# display.net
KiCad netlist of a schematic drawn in Altium Designer
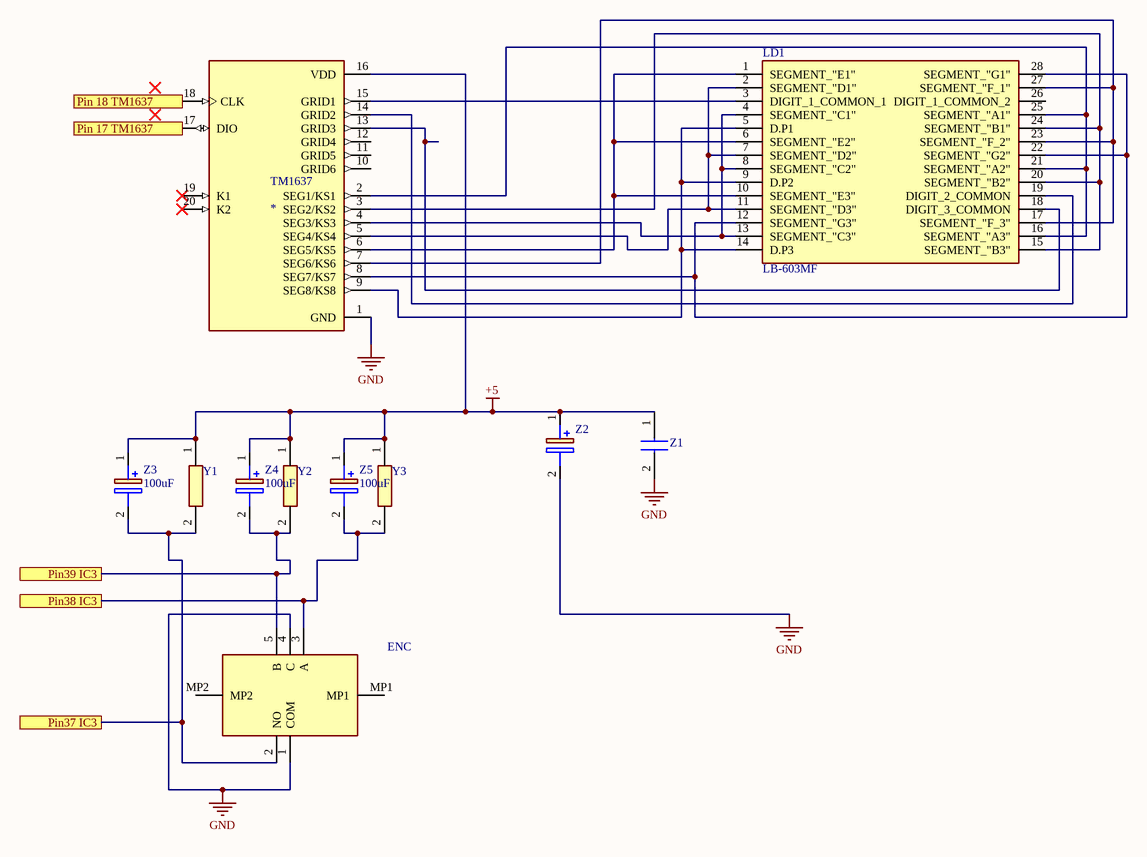
[diagram p0: display.SchDoc]

(export (version "E")
  (design (tool "Eeschema 10.0.6"))
  (components
    (comp (ref "ENC")
      (value "482016514001")
      (footprint "SamacSys:482016514001")
      (description "Switch")
      (fields (field (name "MOUSER2 PART NUMBER") "710-482016514001"))
      (libsource (lib "SamacSys") (part "482016514001"))
    )
    (comp (ref "LD1")
      (value "LB-603MF")
      (footprint "SamacSys:DIP1524W50P254L3750H820Q28N")
      (description "Display")
      (libsource (lib "*") (part "LB-603MF"))
    )
    (comp (ref "TM1637")
      (value "*")
      (footprint "DIP778W43P254L2612H431Q20N")
      (description "LED Drive Control Special Circuit")
      (fields (field (name "MF") "Titan Micro Electronics") (field (name "MP") "TM1637"))
      (libsource (lib "*") (part "TM1637"))
    )
    (comp (ref "Y1")
      (value "ESR10EZPJ183")
      (footprint "SamacSys:RESC2012X60N")
      (description "Resistor SMD 0805 10k")
      (libsource (lib "*") (part "ESR10EZPJ183"))
    )
    (comp (ref "Y2")
      (value "ESR10EZPJ183")
      (footprint "SamacSys:RESC2012X60N")
      (description "Resistor SMD 0805 10k")
      (libsource (lib "*") (part "ESR10EZPJ183"))
    )
    (comp (ref "Y3")
      (value "ESR10EZPJ183")
      (footprint "SamacSys:RESC2012X60N")
      (description "Resistor SMD 0805 10k")
      (libsource (lib "*") (part "ESR10EZPJ183"))
    )
    (comp (ref "Z1")
      (value "860010683032")
      (footprint "SamacSys:CAPPRD200W55D500H1200")
      (description "Capacitor C1")
      (libsource (lib "*") (part "860010683032"))
    )
    (comp (ref "Z2")
      (value "860240672002")
      (footprint "SamacSys:CAPC2012X90N")
      (description "Capacitor Polarised")
      (libsource (lib "*") (part "860240672002"))
    )
    (comp (ref "Z3")
      (value "100uF")
      (footprint "SamacSys:CAPC2012X90N")
      (description "Capacitor Polarised C4 3,5mm 8x11mm")
      (fields (field (name "MANUFACTURER_PART_NUMBER") "ECA-1HHG2R2B"))
      (libsource (lib "*") (part "ECA-1HHG2R2B"))
    )
    (comp (ref "Z4")
      (value "100uF")
      (footprint "SamacSys:CAPC2012X90N")
      (description "Capacitor Polarised C4 3,5mm 8x11mm")
      (fields (field (name "MANUFACTURER_PART_NUMBER") "ECA-1HHG2R2B"))
      (libsource (lib "*") (part "ECA-1HHG2R2B"))
    )
    (comp (ref "Z5")
      (value "100uF")
      (footprint "SamacSys:CAPC2012X90N")
      (description "Capacitor Polarised C4 3,5mm 8x11mm")
      (fields (field (name "MANUFACTURER_PART_NUMBER") "ECA-1HHG2R2B"))
      (libsource (lib "*") (part "ECA-1HHG2R2B"))
    )
  )
  (nets
    (net (code "1") (name "+5") (class "Default")
      (node (ref "TM1637") (pin "16") (pinfunction "VDD_16") (pintype "passive"))
      (node (ref "Y1") (pin "1") (pinfunction "1_1") (pintype "passive"))
      (node (ref "Y2") (pin "1") (pinfunction "1_1") (pintype "passive"))
      (node (ref "Y3") (pin "1") (pinfunction "1_1") (pintype "passive"))
      (node (ref "Z1") (pin "1") (pinfunction "+_1") (pintype "power_in"))
      (node (ref "Z2") (pin "1") (pinfunction "+_1") (pintype "passive"))
      (node (ref "Z3") (pin "1") (pinfunction "+_1") (pintype "passive"))
      (node (ref "Z4") (pin "1") (pinfunction "+_1") (pintype "passive"))
      (node (ref "Z5") (pin "1") (pinfunction "+_1") (pintype "passive"))
    )
    (net (code "2") (name "/Pin 17 TM1637") (class "Default")
      (node (ref "TM1637") (pin "17") (pinfunction "DIO_17") (pintype "bidirectional"))
    )
    (net (code "3") (name "/Pin 18 TM1637") (class "Default")
      (node (ref "TM1637") (pin "18") (pinfunction "CLK_18") (pintype "input"))
    )
    (net (code "4") (name "/Pin37 IC3") (class "Default")
      (node (ref "ENC") (pin "2") (pinfunction "NO_2") (pintype "passive"))
      (node (ref "Y1") (pin "2") (pinfunction "2_2") (pintype "passive"))
      (node (ref "Z3") (pin "2") (pinfunction "-_2") (pintype "passive"))
    )
    (net (code "5") (name "/Pin38 IC3") (class "Default")
      (node (ref "ENC") (pin "3") (pinfunction "A_3") (pintype "passive"))
      (node (ref "Y3") (pin "2") (pinfunction "2_2") (pintype "passive"))
      (node (ref "Z5") (pin "2") (pinfunction "-_2") (pintype "passive"))
    )
    (net (code "6") (name "/Pin39 IC3") (class "Default")
      (node (ref "ENC") (pin "5") (pinfunction "B_5") (pintype "passive"))
      (node (ref "Y2") (pin "2") (pinfunction "2_2") (pintype "passive"))
      (node (ref "Z4") (pin "2") (pinfunction "-_2") (pintype "passive"))
    )
    (net (code "7") (name "GND") (class "Default")
      (node (ref "ENC") (pin "1") (pinfunction "COM_1") (pintype "passive"))
      (node (ref "ENC") (pin "4") (pinfunction "C_4") (pintype "passive"))
      (node (ref "TM1637") (pin "1") (pinfunction "GND_1") (pintype "power_in"))
      (node (ref "Z1") (pin "2") (pinfunction "-_2") (pintype "power_in"))
      (node (ref "Z2") (pin "2") (pinfunction "-_2") (pintype "passive"))
    )
    (net (code "8") (name "Net-(LD1-D.P1)") (class "Default")
      (node (ref "LD1") (pin "14") (pinfunction "D.P3_14") (pintype "passive"))
      (node (ref "LD1") (pin "5") (pinfunction "D.P1_5") (pintype "passive"))
      (node (ref "LD1") (pin "9") (pinfunction "D.P2_9") (pintype "passive"))
      (node (ref "TM1637") (pin "9") (pinfunction "SEG8/KS8_9") (pintype "output"))
    )
    (net (code "9") (name "Net-(LD1-DIGIT_1_COMMON_1)") (class "Default")
      (node (ref "LD1") (pin "3") (pinfunction "DIGIT_1_COMMON_1_3") (pintype "passive"))
      (node (ref "TM1637") (pin "15") (pinfunction "GRID1_15") (pintype "output"))
    )
    (net (code "10") (name "Net-(LD1-DIGIT_2_COMMON)") (class "Default")
      (node (ref "LD1") (pin "19") (pinfunction "DIGIT_2_COMMON_19") (pintype "passive"))
      (node (ref "TM1637") (pin "14") (pinfunction "GRID2_14") (pintype "output"))
    )
    (net (code "11") (name "Net-(LD1-DIGIT_3_COMMON)") (class "Default")
      (node (ref "LD1") (pin "18") (pinfunction "DIGIT_3_COMMON_18") (pintype "passive"))
      (node (ref "TM1637") (pin "13") (pinfunction "GRID3_13") (pintype "output"))
    )
    (net (code "12") (name "Net-(LD1-SEGMENT_\"A1\")") (class "Default")
      (node (ref "LD1") (pin "16") (pinfunction "SEGMENT_\"A3\"_16") (pintype "passive"))
      (node (ref "LD1") (pin "21") (pinfunction "SEGMENT_\"A2\"_21") (pintype "passive"))
      (node (ref "LD1") (pin "25") (pinfunction "SEGMENT_\"A1\"_25") (pintype "passive"))
      (node (ref "TM1637") (pin "2") (pinfunction "SEG1/KS1_2") (pintype "output"))
    )
    (net (code "13") (name "Net-(LD1-SEGMENT_\"B1\")") (class "Default")
      (node (ref "LD1") (pin "15") (pinfunction "SEGMENT_\"B3\"_15") (pintype "passive"))
      (node (ref "LD1") (pin "20") (pinfunction "SEGMENT_\"B2\"_20") (pintype "passive"))
      (node (ref "LD1") (pin "24") (pinfunction "SEGMENT_\"B1\"_24") (pintype "passive"))
      (node (ref "TM1637") (pin "3") (pinfunction "SEG2/KS2_3") (pintype "output"))
    )
    (net (code "14") (name "Net-(LD1-SEGMENT_\"C1\")") (class "Default")
      (node (ref "LD1") (pin "13") (pinfunction "SEGMENT_\"C3\"_13") (pintype "passive"))
      (node (ref "LD1") (pin "4") (pinfunction "SEGMENT_\"C1\"_4") (pintype "passive"))
      (node (ref "LD1") (pin "8") (pinfunction "SEGMENT_\"C2\"_8") (pintype "passive"))
      (node (ref "TM1637") (pin "4") (pinfunction "SEG3/KS3_4") (pintype "output"))
    )
    (net (code "15") (name "Net-(LD1-SEGMENT_\"D1\")") (class "Default")
      (node (ref "LD1") (pin "11") (pinfunction "SEGMENT_\"D3\"_11") (pintype "passive"))
      (node (ref "LD1") (pin "2") (pinfunction "SEGMENT_\"D1\"_2") (pintype "passive"))
      (node (ref "LD1") (pin "7") (pinfunction "SEGMENT_\"D2\"_7") (pintype "passive"))
      (node (ref "TM1637") (pin "5") (pinfunction "SEG4/KS4_5") (pintype "output"))
    )
    (net (code "16") (name "Net-(LD1-SEGMENT_\"E1\")") (class "Default")
      (node (ref "LD1") (pin "1") (pinfunction "SEGMENT_\"E1\"_1") (pintype "passive"))
      (node (ref "LD1") (pin "10") (pinfunction "SEGMENT_\"E3\"_10") (pintype "passive"))
      (node (ref "LD1") (pin "6") (pinfunction "SEGMENT_\"E2\"_6") (pintype "passive"))
      (node (ref "TM1637") (pin "6") (pinfunction "SEG5/KS5_6") (pintype "output"))
    )
    (net (code "17") (name "Net-(LD1-SEGMENT_\"F_1\")") (class "Default")
      (node (ref "LD1") (pin "17") (pinfunction "SEGMENT_\"F_3\"_17") (pintype "passive"))
      (node (ref "LD1") (pin "23") (pinfunction "SEGMENT_\"F_2\"_23") (pintype "passive"))
      (node (ref "LD1") (pin "27") (pinfunction "SEGMENT_\"F_1\"_27") (pintype "passive"))
      (node (ref "TM1637") (pin "7") (pinfunction "SEG6/KS6_7") (pintype "output"))
    )
    (net (code "18") (name "Net-(LD1-SEGMENT_\"G1\")") (class "Default")
      (node (ref "LD1") (pin "12") (pinfunction "SEGMENT_\"G3\"_12") (pintype "passive"))
      (node (ref "LD1") (pin "22") (pinfunction "SEGMENT_\"G2\"_22") (pintype "passive"))
      (node (ref "LD1") (pin "28") (pinfunction "SEGMENT_\"G1\"_28") (pintype "passive"))
      (node (ref "TM1637") (pin "8") (pinfunction "SEG7/KS7_8") (pintype "output"))
    )
    (net (code "19") (name "unconnected-(ENC-PadMP1)") (class "Default")
      (node (ref "ENC") (pin "MP1") (pinfunction "MP1_MP1") (pintype "passive"))
    )
    (net (code "20") (name "unconnected-(ENC-PadMP2)") (class "Default")
      (node (ref "ENC") (pin "MP2") (pinfunction "MP2_MP2") (pintype "passive"))
    )
    (net (code "21") (name "unconnected-(LD1-DIGIT_1_COMMON_2-Pad26)") (class "Default")
      (node (ref "LD1") (pin "26") (pinfunction "DIGIT_1_COMMON_2_26") (pintype "passive"))
    )
    (net (code "22") (name "unconnected-(TM1637-GRID4-Pad12)") (class "Default")
      (node (ref "TM1637") (pin "12") (pinfunction "GRID4_12") (pintype "output"))
    )
    (net (code "23") (name "unconnected-(TM1637-GRID5-Pad11)") (class "Default")
      (node (ref "TM1637") (pin "11") (pinfunction "GRID5_11") (pintype "output"))
    )
    (net (code "24") (name "unconnected-(TM1637-GRID6-Pad10)") (class "Default")
      (node (ref "TM1637") (pin "10") (pinfunction "GRID6_10") (pintype "output"))
    )
    (net (code "25") (name "unconnected-(TM1637-K1-Pad19)") (class "Default")
      (node (ref "TM1637") (pin "19") (pinfunction "K1_19") (pintype "input+no_connect"))
    )
    (net (code "26") (name "unconnected-(TM1637-K2-Pad20)") (class "Default")
      (node (ref "TM1637") (pin "20") (pinfunction "K2_20") (pintype "input+no_connect"))
    )
  )
)
